# Protection_channel_B_Page_3.net
KiCad netlist of a schematic drawn in Altium Designer
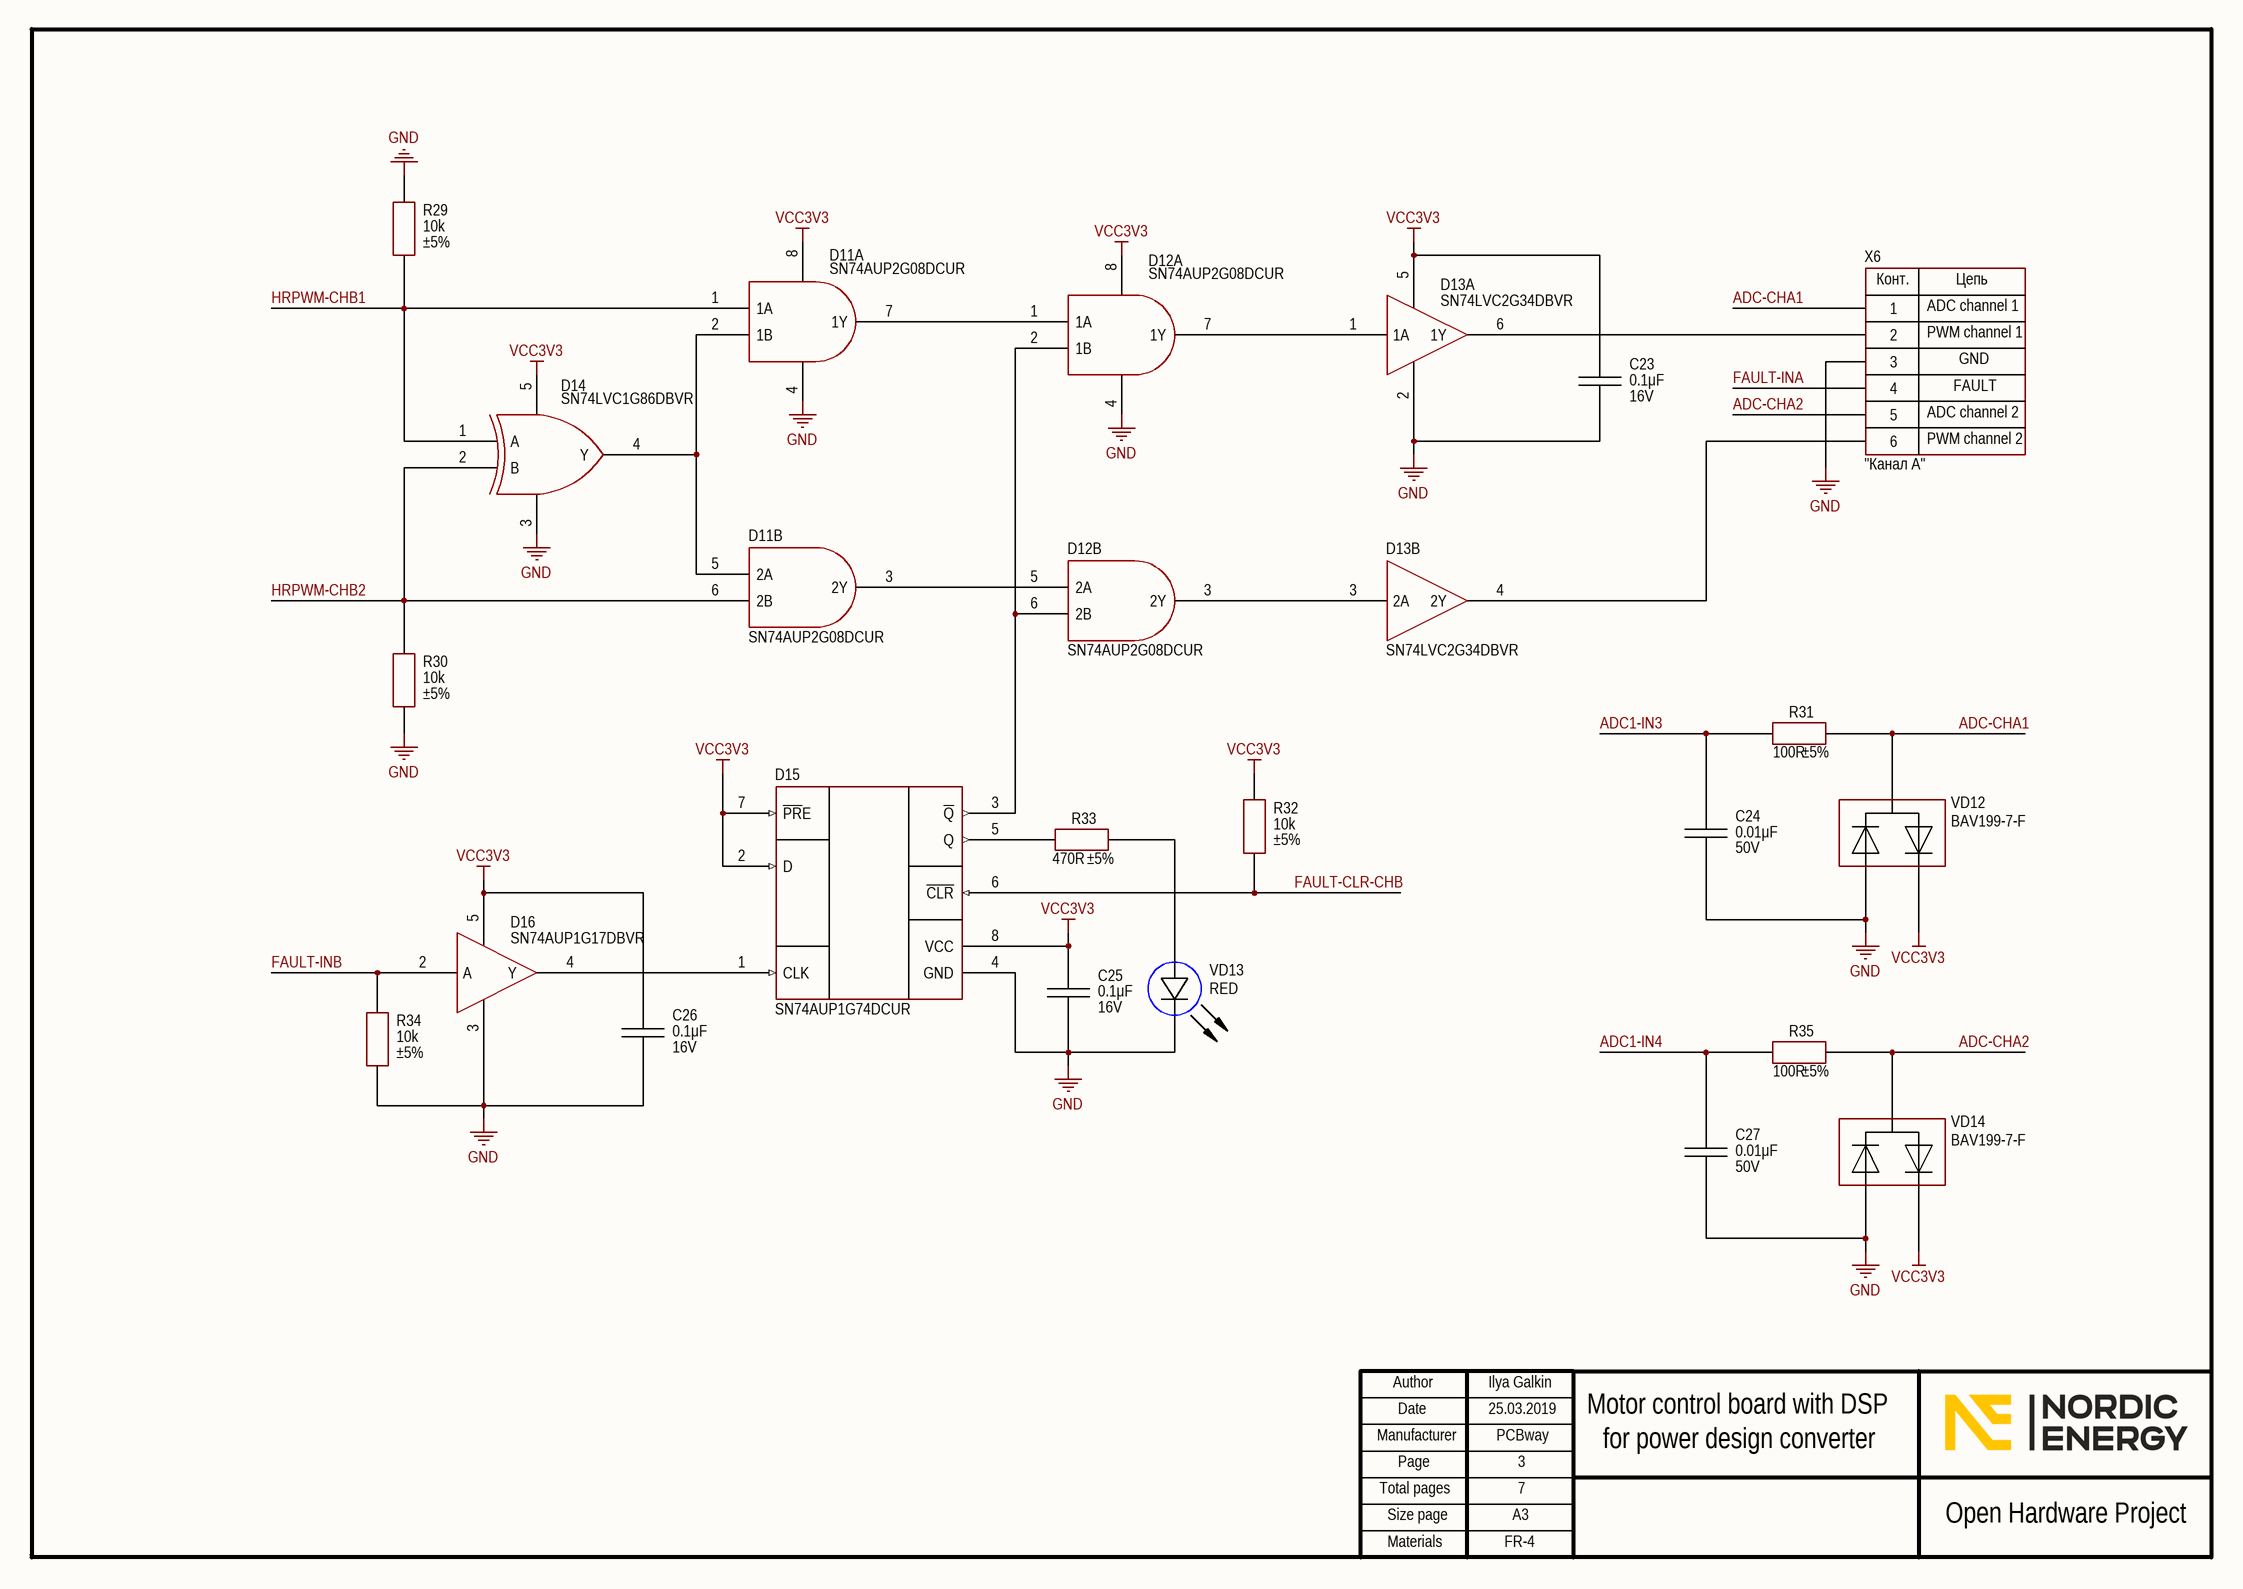
[diagram p0: Protection channel B. Page 3.SchDoc]

(export (version "E")
  (design (tool "Eeschema 10.0.6"))
  (components
    (comp (ref "C23")
      (value "0.1μF")
      (footprint "CAP: 0805")
      (fields
        (field (name "MANUFACTURER") "Yageo")
        (field (name "PARTNUMBER") "CC0805KRX7R7BB104")
        (field (name "VALUEMANUFACTURERPARTNUMBER") "Ceramic capacitor, 0.1μF, X7R, ±10%, 16V, 0805, -55...+125°C")
        (field (name "VOLTAGE") "16V")
      )
      (libsource (lib "Capacitor") (part "Ceramic_0805"))
    )
    (comp (ref "C24")
      (value "0.01μF")
      (footprint "CAP: 0805")
      (fields
        (field (name "MANUFACTURER") "Yageo")
        (field (name "PARTNUMBER") "CC0805KRX7R9BB103")
        (field (name "VALUEMANUFACTURERPARTNUMBER") "Ceramic capacitor, 0.01μF, X7R, ±10%, 50V, 0805, -55...+125°C")
        (field (name "VOLTAGE") "50V")
      )
      (libsource (lib "Capacitor") (part "Ceramic_0805"))
    )
    (comp (ref "C25")
      (value "0.1μF")
      (footprint "CAP: 0805")
      (fields
        (field (name "MANUFACTURER") "Yageo")
        (field (name "PARTNUMBER") "CC0805KRX7R7BB104")
        (field (name "VALUEMANUFACTURERPARTNUMBER") "Ceramic capacitor, 0.1μF, X7R, ±10%, 16V, 0805, -55...+125°C")
        (field (name "VOLTAGE") "16V")
      )
      (libsource (lib "Capacitor") (part "Ceramic_0805"))
    )
    (comp (ref "C26")
      (value "0.1μF")
      (footprint "CAP: 0805")
      (fields
        (field (name "MANUFACTURER") "Yageo")
        (field (name "PARTNUMBER") "CC0805KRX7R7BB104")
        (field (name "VALUEMANUFACTURERPARTNUMBER") "Ceramic capacitor, 0.1μF, X7R, ±10%, 16V, 0805, -55...+125°C")
        (field (name "VOLTAGE") "16V")
      )
      (libsource (lib "Capacitor") (part "Ceramic_0805"))
    )
    (comp (ref "C27")
      (value "0.01μF")
      (footprint "CAP: 0805")
      (fields
        (field (name "MANUFACTURER") "Yageo")
        (field (name "PARTNUMBER") "CC0805KRX7R9BB103")
        (field (name "VALUEMANUFACTURERPARTNUMBER") "Ceramic capacitor, 0.01μF, X7R, ±10%, 50V, 0805, -55...+125°C")
        (field (name "VOLTAGE") "50V")
      )
      (libsource (lib "Capacitor") (part "Ceramic_0805"))
    )
    (comp (ref "D11")
      (value "~")
      (footprint "8-VSSOP")
      (description "AND")
      (fields
        (field (name "MANUFACTURER") "Texas Instruments")
        (field (name "VALUEMANUFACTURERPARTNUMBER") "IC logic AND, 0.8...3.6V, -40...+855°C, 8-VSSOP")
        (field (name "PARTNUMBER") "SN74AUP2G08DCUR")
      )
      (libsource (lib "IC. Logic") (part "SN74AUP2G08DCUR"))
    )
    (comp (ref "D12")
      (value "~")
      (footprint "8-VSSOP")
      (description "AND")
      (fields
        (field (name "MANUFACTURER") "Texas Instruments")
        (field (name "VALUEMANUFACTURERPARTNUMBER") "IC logic AND, 0.8...3.6V, -40...+855°C, 8-VSSOP")
        (field (name "PARTNUMBER") "SN74AUP2G08DCUR")
      )
      (libsource (lib "IC. Logic") (part "SN74AUP2G08DCUR"))
    )
    (comp (ref "D13")
      (value "~")
      (footprint "SOT23-6")
      (description "Buffer")
      (fields
        (field (name "MANUFACTURER") "Texas Instruments")
        (field (name "VALUEMANUFACTURERPARTNUMBER") "IC logic buffer, 1.65...5.5V, -40...+125°C, SOT23-6")
        (field (name "PARTNUMBER") "SN74LVC2G34DBVR")
      )
      (libsource (lib "IC. Logic") (part "SN74LVC2G34DBVR"))
    )
    (comp (ref "D14")
      (value "~")
      (footprint "SOT23-5")
      (description "XOR")
      (fields
        (field (name "MANUFACTURER") "Texas Instruments")
        (field (name "VALUEMANUFACTURERPARTNUMBER") "IC logic XOR, 1.65...5.5V, -40...+125°C, SOT23-5")
        (field (name "PARTNUMBER") "SN74LVC1G86DBVR")
      )
      (libsource (lib "IC. Logic") (part "SN74LVC1G86DBVR"))
    )
    (comp (ref "D15")
      (value "~")
      (footprint "8-VSSOP")
      (description "D-trigger")
      (fields
        (field (name "MANUFACTURER") "Texas Instruments")
        (field (name "VALUEMANUFACTURERPARTNUMBER") "ICtrigger D-type, 0.8...3.6V, -40...+85°C, 8-VSSOP")
        (field (name "PARTNUMBER") "SN74AUP1G74DCUR")
      )
      (libsource (lib "IC. Logic") (part "SN74AUP1G74DCUR"))
    )
    (comp (ref "D16")
      (value "~")
      (footprint "SOT23-5")
      (description "Schmitt trigger")
      (fields
        (field (name "MANUFACTURER") "Texas Instruments")
        (field (name "VALUEMANUFACTURERPARTNUMBER") "IC Schmitt trigger, 0.8...3.6V, -40...+85°C, SOT23-6")
        (field (name "PARTNUMBER") "SN74AUP1G17DBVR")
      )
      (libsource (lib "IC. Logic") (part "SN74AUP1G17DBVR"))
    )
    (comp (ref "R29")
      (value "10k")
      (footprint "RES: 0805")
      (fields
        (field (name "MANUFACTURER") "Yageo")
        (field (name "PARTNUMBER") "RC0805JR-0710KL")
        (field (name "VALUEMANUFACTURERPARTNUMBER") "Resistor film, 10k, ±5%, 0805, 0.125W, -55...+125°C")
        (field (name "TOLERANCE") "±5%")
      )
      (libsource (lib "Resistor") (part "Resistor_0805"))
    )
    (comp (ref "R30")
      (value "10k")
      (footprint "RES: 0805")
      (fields
        (field (name "MANUFACTURER") "Yageo")
        (field (name "PARTNUMBER") "RC0805JR-0710KL")
        (field (name "VALUEMANUFACTURERPARTNUMBER") "Resistor film, 10k, ±5%, 0805, 0.125W, -55...+125°C")
        (field (name "TOLERANCE") "±5%")
      )
      (libsource (lib "Resistor") (part "Resistor_0805"))
    )
    (comp (ref "R31")
      (value "100R")
      (footprint "RES: 0805")
      (fields
        (field (name "MANUFACTURER") "Yageo")
        (field (name "PARTNUMBER") "RC0805JR-07100RL")
        (field (name "VALUEMANUFACTURERPARTNUMBER") "Resistor film, 100R, ±5%, 0805, 0.125W, -55...+125°C")
        (field (name "TOLERANCE") "±5%")
      )
      (libsource (lib "") (part "Resistor_0805_1"))
    )
    (comp (ref "R32")
      (value "10k")
      (footprint "RES: 0805")
      (fields
        (field (name "MANUFACTURER") "Yageo")
        (field (name "PARTNUMBER") "RC0805JR-0710KL")
        (field (name "VALUEMANUFACTURERPARTNUMBER") "Resistor film, 10k, ±5%, 0805, 0.125W, -55...+125°C")
        (field (name "TOLERANCE") "±5%")
      )
      (libsource (lib "Resistor") (part "Resistor_0805"))
    )
    (comp (ref "R33")
      (value "470R")
      (footprint "RES: 0805")
      (fields
        (field (name "MANUFACTURER") "Yageo")
        (field (name "PARTNUMBER") "RC0805JR-07470RL")
        (field (name "VALUEMANUFACTURERPARTNUMBER") "Resistor film, 470R, ±5%, 0805, 0.125W, -55...+125°C")
        (field (name "TOLERANCE") "±5%")
      )
      (libsource (lib "") (part "Resistor_0805_2"))
    )
    (comp (ref "R34")
      (value "10k")
      (footprint "RES: 0805")
      (fields
        (field (name "MANUFACTURER") "Yageo")
        (field (name "PARTNUMBER") "RC0805JR-0710KL")
        (field (name "VALUEMANUFACTURERPARTNUMBER") "Resistor film, 10k, ±5%, 0805, 0.125W, -55...+125°C")
        (field (name "TOLERANCE") "±5%")
      )
      (libsource (lib "Resistor") (part "Resistor_0805"))
    )
    (comp (ref "R35")
      (value "100R")
      (footprint "RES: 0805")
      (fields
        (field (name "MANUFACTURER") "Yageo")
        (field (name "PARTNUMBER") "RC0805JR-07100RL")
        (field (name "VALUEMANUFACTURERPARTNUMBER") "Resistor film, 100R, ±5%, 0805, 0.125W, -55...+125°C")
        (field (name "TOLERANCE") "±5%")
      )
      (libsource (lib "") (part "Resistor_0805_1"))
    )
    (comp (ref "VD12")
      (value "~")
      (footprint "SOT23")
      (fields
        (field (name "MANUFACTURER") "Diodes Incorporated")
        (field (name "VALUEMANUFACTURERPARTNUMBER") "Diode array, 85V, 140mA, 1.1V, 3us, SOT-23, -65...+150°C")
        (field (name "VOLTAGE") "85V")
        (field (name "PARTNUMBER") "BAV199-7-F")
      )
      (libsource (lib "Diode") (part "Diode_array"))
    )
    (comp (ref "VD13")
      (value "~")
      (footprint "LED: 0805R")
      (fields
        (field (name "MANUFACTURER") "Wurth")
        (field (name "VALUEMANUFACTURERPARTNUMBER") "LED, 20mA, 2V, 0805, -55...+150°C")
        (field (name "PARTNUMBER") "150080RS75000")
        (field (name "COLOR") "RED")
      )
      (libsource (lib "Diode") (part "LED_single"))
    )
    (comp (ref "VD14")
      (value "~")
      (footprint "SOT23")
      (fields
        (field (name "MANUFACTURER") "Diodes Incorporated")
        (field (name "VALUEMANUFACTURERPARTNUMBER") "Diode array, 85V, 140mA, 1.1V, 3us, SOT-23, -65...+150°C")
        (field (name "VOLTAGE") "85V")
        (field (name "PARTNUMBER") "BAV199-7-F")
      )
      (libsource (lib "Diode") (part "Diode_array"))
    )
    (comp (ref "X6")
      (value "~")
      (footprint "CON: PLD-6")
      (fields
        (field (name "MANUFACTURER") "Connfly")
        (field (name "VALUEMANUFACTURERPARTNUMBER") "Connector, 6pin, 2.54mm, 500VAC, 3A")
        (field (name "PARTNUMBER") "PLD-6")
        (field (name "COMMENTTEXT") "\"Канал А\"")
      )
      (libsource (lib "Connector") (part "PLD-6"))
    )
  )
  (nets
    (net (code "1") (name "/ADC-CHA1") (class "Default")
      (node (ref "R31") (pin "2") (pinfunction "2_2") (pintype "passive"))
      (node (ref "VD12") (pin "3") (pinfunction "3_3") (pintype "passive"))
      (node (ref "X6") (pin "1") (pinfunction "1_1") (pintype "passive"))
    )
    (net (code "2") (name "/ADC-CHA2") (class "Default")
      (node (ref "R35") (pin "2") (pinfunction "2_2") (pintype "passive"))
      (node (ref "VD14") (pin "3") (pinfunction "3_3") (pintype "passive"))
      (node (ref "X6") (pin "5") (pinfunction "5_5") (pintype "power_in"))
    )
    (net (code "3") (name "/ADC1-IN3") (class "Default")
      (node (ref "C24") (pin "2") (pinfunction "2_2") (pintype "power_in"))
      (node (ref "R31") (pin "1") (pinfunction "1_1") (pintype "passive"))
    )
    (net (code "4") (name "/ADC1-IN4") (class "Default")
      (node (ref "C27") (pin "2") (pinfunction "2_2") (pintype "power_in"))
      (node (ref "R35") (pin "1") (pinfunction "1_1") (pintype "passive"))
    )
    (net (code "5") (name "/FAULT-CLR-CHB") (class "Default")
      (node (ref "D15") (pin "6") (pinfunction "~{CLR}_6") (pintype "input"))
      (node (ref "R32") (pin "2") (pinfunction "2_2") (pintype "passive"))
    )
    (net (code "6") (name "/FAULT-INA") (class "Default")
      (node (ref "X6") (pin "4") (pinfunction "4_4") (pintype "power_in"))
    )
    (net (code "7") (name "/FAULT-INB") (class "Default")
      (node (ref "D16") (pin "2") (pinfunction "A_2") (pintype "passive"))
      (node (ref "R34") (pin "1") (pinfunction "1_1") (pintype "passive"))
    )
    (net (code "8") (name "/HRPWM-CHB1") (class "Default")
      (node (ref "D11") (pin "1") (pinfunction "1A_1") (pintype "passive"))
      (node (ref "D14") (pin "1") (pinfunction "A_1") (pintype "passive"))
      (node (ref "R29") (pin "2") (pinfunction "2_2") (pintype "passive"))
    )
    (net (code "9") (name "/HRPWM-CHB2") (class "Default")
      (node (ref "D11") (pin "6") (pinfunction "2B_6") (pintype "passive"))
      (node (ref "D14") (pin "2") (pinfunction "B_2") (pintype "passive"))
      (node (ref "R30") (pin "1") (pinfunction "1_1") (pintype "passive"))
    )
    (net (code "10") (name "GND") (class "Default")
      (node (ref "C23") (pin "1") (pinfunction "1_1") (pintype "power_in"))
      (node (ref "C24") (pin "1") (pinfunction "1_1") (pintype "power_in"))
      (node (ref "C25") (pin "1") (pinfunction "1_1") (pintype "power_in"))
      (node (ref "C26") (pin "1") (pinfunction "1_1") (pintype "power_in"))
      (node (ref "C27") (pin "1") (pinfunction "1_1") (pintype "power_in"))
      (node (ref "D11") (pin "4") (pintype "passive"))
      (node (ref "D12") (pin "4") (pintype "passive"))
      (node (ref "D13") (pin "2") (pintype "passive"))
      (node (ref "D14") (pin "3") (pintype "passive"))
      (node (ref "D15") (pin "4") (pinfunction "GND_4") (pintype "passive"))
      (node (ref "D16") (pin "3") (pintype "passive"))
      (node (ref "R29") (pin "1") (pinfunction "1_1") (pintype "passive"))
      (node (ref "R30") (pin "2") (pinfunction "2_2") (pintype "passive"))
      (node (ref "R34") (pin "2") (pinfunction "2_2") (pintype "passive"))
      (node (ref "VD12") (pin "1") (pinfunction "1_1") (pintype "passive"))
      (node (ref "VD13") (pin "2") (pinfunction "C_2") (pintype "passive"))
      (node (ref "VD14") (pin "1") (pinfunction "1_1") (pintype "passive"))
      (node (ref "X6") (pin "3") (pinfunction "3_3") (pintype "power_in"))
    )
    (net (code "11") (name "Net-(D11A-1B)") (class "Default")
      (node (ref "D11") (pin "2") (pinfunction "1B_2") (pintype "passive"))
      (node (ref "D11") (pin "5") (pinfunction "2A_5") (pintype "passive"))
      (node (ref "D14") (pin "4") (pinfunction "Y_4") (pintype "passive"))
    )
    (net (code "12") (name "Net-(D11A-1Y)") (class "Default")
      (node (ref "D11") (pin "7") (pinfunction "1Y_7") (pintype "passive"))
      (node (ref "D12") (pin "1") (pinfunction "1A_1") (pintype "passive"))
    )
    (net (code "13") (name "Net-(D11B-2Y)") (class "Default")
      (node (ref "D11") (pin "3") (pinfunction "2Y_3") (pintype "passive"))
      (node (ref "D12") (pin "5") (pinfunction "2A_5") (pintype "passive"))
    )
    (net (code "14") (name "Net-(D12A-1B)") (class "Default")
      (node (ref "D12") (pin "2") (pinfunction "1B_2") (pintype "passive"))
      (node (ref "D12") (pin "6") (pinfunction "2B_6") (pintype "passive"))
      (node (ref "D15") (pin "3") (pinfunction "~{Q}_3") (pintype "output"))
    )
    (net (code "15") (name "Net-(D12A-1Y)") (class "Default")
      (node (ref "D12") (pin "7") (pinfunction "1Y_7") (pintype "passive"))
      (node (ref "D13") (pin "1") (pinfunction "1A_1") (pintype "passive"))
    )
    (net (code "16") (name "Net-(D12B-2Y)") (class "Default")
      (node (ref "D12") (pin "3") (pinfunction "2Y_3") (pintype "passive"))
      (node (ref "D13") (pin "3") (pinfunction "2A_3") (pintype "passive"))
    )
    (net (code "17") (name "Net-(D13A-1Y)") (class "Default")
      (node (ref "D13") (pin "6") (pinfunction "1Y_6") (pintype "passive"))
      (node (ref "X6") (pin "2") (pinfunction "2_2") (pintype "passive"))
    )
    (net (code "18") (name "Net-(D13B-2Y)") (class "Default")
      (node (ref "D13") (pin "4") (pinfunction "2Y_4") (pintype "passive"))
      (node (ref "X6") (pin "6") (pinfunction "6_6") (pintype "power_in"))
    )
    (net (code "19") (name "Net-(D15-CLK)") (class "Default")
      (node (ref "D15") (pin "1") (pinfunction "CLK_1") (pintype "input"))
      (node (ref "D16") (pin "4") (pinfunction "Y_4") (pintype "passive"))
    )
    (net (code "20") (name "Net-(D15-Q)") (class "Default")
      (node (ref "D15") (pin "5") (pinfunction "Q_5") (pintype "output"))
      (node (ref "R33") (pin "2") (pinfunction "2_2") (pintype "passive"))
    )
    (net (code "21") (name "Net-(VD13-A)") (class "Default")
      (node (ref "R33") (pin "1") (pinfunction "1_1") (pintype "passive"))
      (node (ref "VD13") (pin "1") (pinfunction "A_1") (pintype "passive"))
    )
    (net (code "22") (name "VCC3V3") (class "Default")
      (node (ref "C23") (pin "2") (pinfunction "2_2") (pintype "power_in"))
      (node (ref "C25") (pin "2") (pinfunction "2_2") (pintype "power_in"))
      (node (ref "C26") (pin "2") (pinfunction "2_2") (pintype "power_in"))
      (node (ref "D11") (pin "8") (pintype "passive"))
      (node (ref "D12") (pin "8") (pintype "passive"))
      (node (ref "D13") (pin "5") (pintype "passive"))
      (node (ref "D14") (pin "5") (pintype "passive"))
      (node (ref "D15") (pin "2") (pinfunction "D_2") (pintype "input"))
      (node (ref "D15") (pin "7") (pinfunction "~{PR}E_7") (pintype "input"))
      (node (ref "D15") (pin "8") (pinfunction "VCC_8") (pintype "passive"))
      (node (ref "D16") (pin "5") (pintype "passive"))
      (node (ref "R32") (pin "1") (pinfunction "1_1") (pintype "passive"))
      (node (ref "VD12") (pin "2") (pinfunction "2_2") (pintype "passive"))
      (node (ref "VD14") (pin "2") (pinfunction "2_2") (pintype "passive"))
    )
  )
)
